# EE579_Skittles_sch.net
KiCad netlist of a schematic drawn in Altium Designer
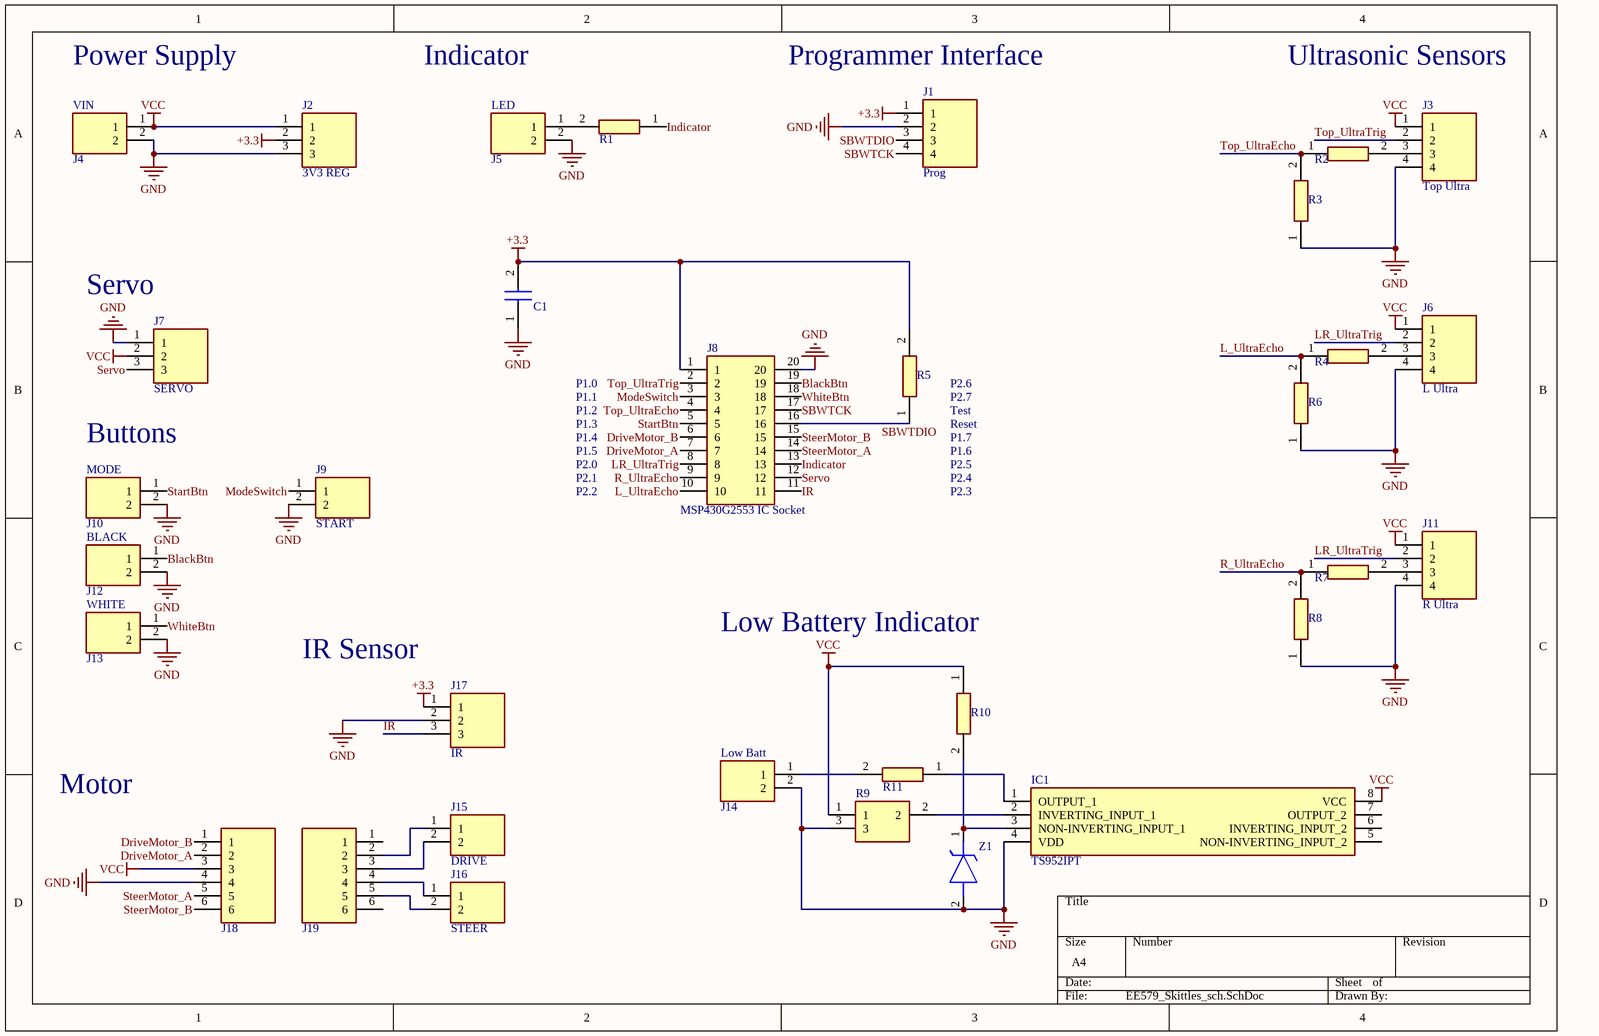
[diagram p0: EE579_Skittles_sch.SchDoc]

(export (version "E")
  (design (tool "Eeschema 10.0.6"))
  (components
    (comp (ref "C1")
      (value "21A106KQFNNNG")
      (footprint "PCB_lib:CAPC2012X135N")
      (description "Capacitor")
      (fields
        (field (name "MANUFACTURER_PART_NUMBER") "CL21A106KQFNNNG")
        (field (name "MOUSER PART NUMBER") "187-CL21A106KQFNNNG")
      )
      (libsource (lib "*") (part "CL21A106KQFNNNG"))
    )
    (comp (ref "IC1")
      (value "TS952IPT")
      (footprint "PCB_lib:SOP65P640X120-8N")
      (description "Integrated Circuit")
      (fields (field (name "MOUSER PART NUMBER") "511-TS952IP"))
      (libsource (lib "*") (part "TS952IPT"))
    )
    (comp (ref "J1")
      (value "Prog")
      (footprint "PCB_lib:HDRV4W64P0X254_1X4_1016X250X901P")
      (description "Connector")
      (fields
        (field (name "MANUFACTURER_PART_NUMBER") "PH1-04-UA")
        (field (name "MOUSER PART NUMBER") "737-PH1-04-UA")
      )
      (libsource (lib "*") (part "PH1-04-UA"))
    )
    (comp (ref "J2")
      (value "3V3 REG")
      (footprint "PCB_lib:RHDR3W60P0X254_1X3_762X254X700P")
      (description "Connector")
      (fields
        (field (name "MANUFACTURER_PART_NUMBER") "801-87-003-10-001101")
        (field (name "MOUSER PART NUMBER") "437-8018700310001101")
      )
      (libsource (lib "*") (part "801-87-003-10-001101"))
    )
    (comp (ref "J3")
      (value "Top Ultra")
      (footprint "PCB_lib:SHDR4W50P0X200_1X4_990X450X600P")
      (description "Connector")
      (fields (field (name "MANUFACTURER_PART_NUMBER") "B4B-PH-K-S(LF)(SN)"))
      (libsource (lib "*") (part "B4B-PH-K-S_LF__SN_"))
    )
    (comp (ref "J4")
      (value "VIN")
      (footprint "PCB_lib:SHDR2W50P0X200_1X2_590X450X600P")
      (description "Connector")
      (fields (field (name "MANUFACTURER_PART_NUMBER") "B2B-PH-K-S(LF)(SN)"))
      (libsource (lib "") (part "B2B-PH-K-S_LF__SN__1"))
    )
    (comp (ref "J5")
      (value "LED")
      (footprint "PCB_lib:SHDR2W50P0X200_1X2_590X450X600P")
      (description "Connector")
      (fields (field (name "MANUFACTURER_PART_NUMBER") "B2B-PH-K-S(LF)(SN)"))
      (libsource (lib "") (part "B2B-PH-K-S_LF__SN__1"))
    )
    (comp (ref "J6")
      (value "L Ultra")
      (footprint "PCB_lib:SHDR4W50P0X200_1X4_990X450X600P")
      (description "Connector")
      (fields (field (name "MANUFACTURER_PART_NUMBER") "B4B-PH-K-S(LF)(SN)"))
      (libsource (lib "*") (part "B4B-PH-K-S_LF__SN_"))
    )
    (comp (ref "J7")
      (value "SERVO")
      (footprint "PCB_lib:RHDR3W60P0X254_1X3_762X254X700P")
      (description "Connector")
      (fields
        (field (name "MANUFACTURER_PART_NUMBER") "801-87-003-10-001101")
        (field (name "MOUSER PART NUMBER") "437-8018700310001101")
      )
      (libsource (lib "*") (part "801-87-003-10-001101"))
    )
    (comp (ref "J8")
      (value "MSP430G2553 IC Socket")
      (footprint "PCB_lib:DIPS762W70P254L2540H510Q20N")
      (description "Connector")
      (fields
        (field (name "MANUFACTURER_PART_NUMBER") "1-2199298-6")
        (field (name "MOUSER PART NUMBER") "571-1-2199298-6")
      )
      (libsource (lib "*") (part "1-2199298-6"))
    )
    (comp (ref "J9")
      (value "START")
      (footprint "PCB_lib:SHDR2W50P0X200_1X2_590X450X600P")
      (description "Connector")
      (fields (field (name "MANUFACTURER_PART_NUMBER") "B2B-PH-K-S(LF)(SN)"))
      (libsource (lib "*") (part "B2B-PH-K-S_LF__SN_"))
    )
    (comp (ref "J10")
      (value "MODE")
      (footprint "PCB_lib:SHDR2W50P0X200_1X2_590X450X600P")
      (description "Connector")
      (fields (field (name "MANUFACTURER_PART_NUMBER") "B2B-PH-K-S(LF)(SN)"))
      (libsource (lib "") (part "B2B-PH-K-S_LF__SN__1"))
    )
    (comp (ref "J11")
      (value "R Ultra")
      (footprint "PCB_lib:SHDR4W50P0X200_1X4_990X450X600P")
      (description "Connector")
      (fields (field (name "MANUFACTURER_PART_NUMBER") "B4B-PH-K-S(LF)(SN)"))
      (libsource (lib "*") (part "B4B-PH-K-S_LF__SN_"))
    )
    (comp (ref "J12")
      (value "BLACK")
      (footprint "PCB_lib:SHDR2W50P0X200_1X2_590X450X600P")
      (description "Connector")
      (fields (field (name "MANUFACTURER_PART_NUMBER") "B2B-PH-K-S(LF)(SN)"))
      (libsource (lib "") (part "B2B-PH-K-S_LF__SN__1"))
    )
    (comp (ref "J13")
      (value "WHITE")
      (footprint "PCB_lib:SHDR2W50P0X200_1X2_590X450X600P")
      (description "Connector")
      (fields (field (name "MANUFACTURER_PART_NUMBER") "B2B-PH-K-S(LF)(SN)"))
      (libsource (lib "") (part "B2B-PH-K-S_LF__SN__1"))
    )
    (comp (ref "J14")
      (value "Low Batt")
      (footprint "PCB_lib:SHDR2W50P0X200_1X2_590X450X600P")
      (description "Connector")
      (fields (field (name "MANUFACTURER_PART_NUMBER") "B2B-PH-K-S(LF)(SN)"))
      (libsource (lib "") (part "B2B-PH-K-S_LF__SN__1"))
    )
    (comp (ref "J15")
      (value "DRIVE")
      (footprint "PCB_lib:SHDR2W50P0X200_1X2_590X450X600P")
      (description "Connector")
      (fields (field (name "MANUFACTURER_PART_NUMBER") "B2B-PH-K-S(LF)(SN)"))
      (libsource (lib "*") (part "B2B-PH-K-S_LF__SN_"))
    )
    (comp (ref "J16")
      (value "STEER")
      (footprint "PCB_lib:SHDR2W50P0X200_1X2_590X450X600P")
      (description "Connector")
      (fields (field (name "MANUFACTURER_PART_NUMBER") "B2B-PH-K-S(LF)(SN)"))
      (libsource (lib "*") (part "B2B-PH-K-S_LF__SN_"))
    )
    (comp (ref "J17")
      (value "IR")
      (footprint "PCB_lib:SHDR3W50P0X200_1X3_790X450X600P")
      (description "Connector")
      (fields (field (name "MANUFACTURER_PART_NUMBER") "B3B-PH-K-S(LF)(SN)"))
      (libsource (lib "*") (part "B3B-PH-K-S_LF__SN_"))
    )
    (comp (ref "J18")
      (value "61300611821")
      (footprint "RHDR6W97P0X254_1X6_1574X250X865P")
      (description "Connector")
      (fields (field (name "MOUSER PART NUMBER") "710-61300611821"))
      (libsource (lib "SCH_lib") (part "61300611821"))
    )
    (comp (ref "J19")
      (value "61300611821")
      (footprint "RHDR6W97P0X254_1X6_1574X250X865P")
      (description "Connector")
      (fields (field (name "MOUSER PART NUMBER") "710-61300611821"))
      (libsource (lib "") (part "61300611821_1"))
    )
    (comp (ref "R1")
      (value "ERJ-PB6B3002V")
      (footprint "PCB_lib:RESC2012X70N")
      (description "Resistor")
      (fields (field (name "MOUSER PART NUMBER") "667-ERJ-PB6B3002V"))
      (libsource (lib "") (part "ERJ-PB6B3002V_3"))
    )
    (comp (ref "R2")
      (value "ERJ-PB6B3002V")
      (footprint "PCB_lib:RESC2012X70N")
      (description "Resistor")
      (fields (field (name "MOUSER PART NUMBER") "667-ERJ-PB6B3002V"))
      (libsource (lib "") (part "ERJ-PB6B3002V_1"))
    )
    (comp (ref "R3")
      (value "ERJ-PB6B3002V")
      (footprint "PCB_lib:RESC2012X70N")
      (description "Resistor")
      (fields (field (name "MOUSER PART NUMBER") "667-ERJ-PB6B3002V"))
      (libsource (lib "*") (part "ERJ-PB6B3002V"))
    )
    (comp (ref "R4")
      (value "ERJ-PB6B3002V")
      (footprint "PCB_lib:RESC2012X70N")
      (description "Resistor")
      (fields (field (name "MOUSER PART NUMBER") "667-ERJ-PB6B3002V"))
      (libsource (lib "") (part "ERJ-PB6B3002V_1"))
    )
    (comp (ref "R5")
      (value "ERJ-PB6B3002V")
      (footprint "PCB_lib:RESC2012X70N")
      (description "Resistor")
      (fields (field (name "MOUSER PART NUMBER") "667-ERJ-PB6B3002V"))
      (libsource (lib "*") (part "ERJ-PB6B3002V"))
    )
    (comp (ref "R6")
      (value "ERJ-PB6B3002V")
      (footprint "PCB_lib:RESC2012X70N")
      (description "Resistor")
      (fields (field (name "MOUSER PART NUMBER") "667-ERJ-PB6B3002V"))
      (libsource (lib "*") (part "ERJ-PB6B3002V"))
    )
    (comp (ref "R7")
      (value "ERJ-PB6B3002V")
      (footprint "PCB_lib:RESC2012X70N")
      (description "Resistor")
      (fields (field (name "MOUSER PART NUMBER") "667-ERJ-PB6B3002V"))
      (libsource (lib "") (part "ERJ-PB6B3002V_1"))
    )
    (comp (ref "R8")
      (value "ERJ-PB6B3002V")
      (footprint "PCB_lib:RESC2012X70N")
      (description "Resistor")
      (fields (field (name "MOUSER PART NUMBER") "667-ERJ-PB6B3002V"))
      (libsource (lib "*") (part "ERJ-PB6B3002V"))
    )
    (comp (ref "R9")
      (value "3314G-1-103E")
      (footprint "PCB_lib:3314G-1-102E")
      (description "Resistor")
      (fields (field (name "MOUSER PART NUMBER") "652-3314G-1-103E"))
      (libsource (lib "*") (part "3314G-1-103E"))
    )
    (comp (ref "R10")
      (value "ERJ-PB6B3002V")
      (footprint "PCB_lib:RESC2012X70N")
      (description "Resistor")
      (fields (field (name "MOUSER PART NUMBER") "667-ERJ-PB6B3002V"))
      (libsource (lib "") (part "ERJ-PB6B3002V_2"))
    )
    (comp (ref "R11")
      (value "ERJ-PB6B3002V")
      (footprint "PCB_lib:RESC2012X70N")
      (description "Resistor")
      (fields (field (name "MOUSER PART NUMBER") "667-ERJ-PB6B3002V"))
      (libsource (lib "") (part "ERJ-PB6B3002V_3"))
    )
    (comp (ref "Z1")
      (value "BZT52C4V7-E3-08")
      (footprint "PCB_lib:SOD3716X135N")
      (description "Zener Diode")
      (fields (field (name "MOUSER PART NUMBER") "78-BZT52C4V7-E3-08"))
      (libsource (lib "*") (part "BZT52C4V7-E3-08"))
    )
  )
  (nets
    (net (code "1") (name "+3.3") (class "Default")
      (node (ref "C1") (pin "2") (pinfunction "2_2") (pintype "passive"))
      (node (ref "J1") (pin "1") (pinfunction "1_1") (pintype "passive"))
      (node (ref "J17") (pin "1") (pinfunction "1_1") (pintype "passive"))
      (node (ref "J2") (pin "2") (pinfunction "2_2") (pintype "passive"))
      (node (ref "J8") (pin "1") (pinfunction "1_1") (pintype "passive"))
      (node (ref "R5") (pin "2") (pinfunction "2_2") (pintype "passive"))
    )
    (net (code "2") (name "/BlackBtn") (class "Default")
      (node (ref "J12") (pin "1") (pinfunction "1_1") (pintype "passive"))
      (node (ref "J8") (pin "19") (pinfunction "19_19") (pintype "passive"))
    )
    (net (code "3") (name "/DriveMotor_A") (class "Default")
      (node (ref "J18") (pin "2") (pinfunction "2_2") (pintype "passive"))
      (node (ref "J8") (pin "7") (pinfunction "7_7") (pintype "passive"))
    )
    (net (code "4") (name "/DriveMotor_B") (class "Default")
      (node (ref "J18") (pin "1") (pinfunction "1_1") (pintype "passive"))
      (node (ref "J8") (pin "6") (pinfunction "6_6") (pintype "passive"))
    )
    (net (code "5") (name "/IR") (class "Default")
      (node (ref "J17") (pin "3") (pinfunction "3_3") (pintype "passive"))
      (node (ref "J8") (pin "11") (pinfunction "11_11") (pintype "passive"))
    )
    (net (code "6") (name "/Indicator") (class "Default")
      (node (ref "J8") (pin "13") (pinfunction "13_13") (pintype "passive"))
      (node (ref "R1") (pin "1") (pinfunction "1_1") (pintype "passive"))
    )
    (net (code "7") (name "/LR_UltraTrig") (class "Default")
      (node (ref "J11") (pin "2") (pinfunction "2_2") (pintype "passive"))
      (node (ref "J6") (pin "2") (pinfunction "2_2") (pintype "passive"))
      (node (ref "J8") (pin "8") (pinfunction "8_8") (pintype "passive"))
    )
    (net (code "8") (name "/L_UltraEcho") (class "Default")
      (node (ref "J8") (pin "10") (pinfunction "10_10") (pintype "passive"))
      (node (ref "R4") (pin "1") (pinfunction "1_1") (pintype "passive"))
      (node (ref "R6") (pin "2") (pinfunction "2_2") (pintype "passive"))
    )
    (net (code "9") (name "/ModeSwitch") (class "Default")
      (node (ref "J8") (pin "3") (pinfunction "3_3") (pintype "passive"))
      (node (ref "J9") (pin "1") (pinfunction "1_1") (pintype "passive"))
    )
    (net (code "10") (name "/R_UltraEcho") (class "Default")
      (node (ref "J8") (pin "9") (pinfunction "9_9") (pintype "passive"))
      (node (ref "R7") (pin "1") (pinfunction "1_1") (pintype "passive"))
      (node (ref "R8") (pin "2") (pinfunction "2_2") (pintype "passive"))
    )
    (net (code "11") (name "/SBWTCK") (class "Default")
      (node (ref "J1") (pin "4") (pinfunction "4_4") (pintype "passive"))
      (node (ref "J8") (pin "17") (pinfunction "17_17") (pintype "passive"))
    )
    (net (code "12") (name "/SBWTDIO") (class "Default")
      (node (ref "J1") (pin "3") (pinfunction "3_3") (pintype "passive"))
      (node (ref "J8") (pin "16") (pinfunction "16_16") (pintype "passive"))
      (node (ref "R5") (pin "1") (pinfunction "1_1") (pintype "passive"))
    )
    (net (code "13") (name "/Servo") (class "Default")
      (node (ref "J7") (pin "3") (pinfunction "3_3") (pintype "passive"))
      (node (ref "J8") (pin "12") (pinfunction "12_12") (pintype "passive"))
    )
    (net (code "14") (name "/StartBtn") (class "Default")
      (node (ref "J10") (pin "1") (pinfunction "1_1") (pintype "passive"))
      (node (ref "J8") (pin "5") (pinfunction "5_5") (pintype "passive"))
    )
    (net (code "15") (name "/SteerMotor_A") (class "Default")
      (node (ref "J18") (pin "5") (pinfunction "5_5") (pintype "passive"))
      (node (ref "J8") (pin "14") (pinfunction "14_14") (pintype "passive"))
    )
    (net (code "16") (name "/SteerMotor_B") (class "Default")
      (node (ref "J18") (pin "6") (pinfunction "6_6") (pintype "passive"))
      (node (ref "J8") (pin "15") (pinfunction "15_15") (pintype "passive"))
    )
    (net (code "17") (name "/Top_UltraEcho") (class "Default")
      (node (ref "J8") (pin "4") (pinfunction "4_4") (pintype "passive"))
      (node (ref "R2") (pin "1") (pinfunction "1_1") (pintype "passive"))
      (node (ref "R3") (pin "2") (pinfunction "2_2") (pintype "passive"))
    )
    (net (code "18") (name "/Top_UltraTrig") (class "Default")
      (node (ref "J3") (pin "2") (pinfunction "2_2") (pintype "passive"))
      (node (ref "J8") (pin "2") (pinfunction "2_2") (pintype "passive"))
    )
    (net (code "19") (name "/WhiteBtn") (class "Default")
      (node (ref "J13") (pin "1") (pinfunction "1_1") (pintype "passive"))
      (node (ref "J8") (pin "18") (pinfunction "18_18") (pintype "passive"))
    )
    (net (code "20") (name "GND") (class "Default")
      (node (ref "C1") (pin "1") (pinfunction "1_1") (pintype "passive"))
      (node (ref "IC1") (pin "4") (pinfunction "VDD_4") (pintype "passive"))
      (node (ref "J1") (pin "2") (pinfunction "2_2") (pintype "passive"))
      (node (ref "J10") (pin "2") (pinfunction "2_2") (pintype "passive"))
      (node (ref "J11") (pin "4") (pinfunction "4_4") (pintype "passive"))
      (node (ref "J12") (pin "2") (pinfunction "2_2") (pintype "passive"))
      (node (ref "J13") (pin "2") (pinfunction "2_2") (pintype "passive"))
      (node (ref "J14") (pin "2") (pinfunction "2_2") (pintype "passive"))
      (node (ref "J17") (pin "2") (pinfunction "2_2") (pintype "passive"))
      (node (ref "J18") (pin "4") (pinfunction "4_4") (pintype "passive"))
      (node (ref "J2") (pin "3") (pinfunction "3_3") (pintype "passive"))
      (node (ref "J3") (pin "4") (pinfunction "4_4") (pintype "passive"))
      (node (ref "J4") (pin "2") (pinfunction "2_2") (pintype "passive"))
      (node (ref "J5") (pin "2") (pinfunction "2_2") (pintype "passive"))
      (node (ref "J6") (pin "4") (pinfunction "4_4") (pintype "passive"))
      (node (ref "J7") (pin "1") (pinfunction "1_1") (pintype "passive"))
      (node (ref "J8") (pin "20") (pinfunction "20_20") (pintype "passive"))
      (node (ref "J9") (pin "2") (pinfunction "2_2") (pintype "passive"))
      (node (ref "R3") (pin "1") (pinfunction "1_1") (pintype "passive"))
      (node (ref "R6") (pin "1") (pinfunction "1_1") (pintype "passive"))
      (node (ref "R8") (pin "1") (pinfunction "1_1") (pintype "passive"))
      (node (ref "R9") (pin "3") (pinfunction "3_3") (pintype "passive"))
      (node (ref "Z1") (pin "2") (pinfunction "A_2") (pintype "passive"))
    )
    (net (code "21") (name "Net-(IC1-INVERTING_INPUT_1)") (class "Default")
      (node (ref "IC1") (pin "2") (pinfunction "INVERTING_INPUT_1_2") (pintype "passive"))
      (node (ref "R9") (pin "2") (pinfunction "2_2") (pintype "passive"))
    )
    (net (code "22") (name "Net-(IC1-NON-INVERTING_INPUT_1)") (class "Default")
      (node (ref "IC1") (pin "3") (pinfunction "NON-INVERTING_INPUT_1_3") (pintype "passive"))
      (node (ref "R10") (pin "2") (pinfunction "2_2") (pintype "passive"))
      (node (ref "Z1") (pin "1") (pinfunction "K_1") (pintype "passive"))
    )
    (net (code "23") (name "Net-(IC1-OUTPUT_1)") (class "Default")
      (node (ref "IC1") (pin "1") (pinfunction "OUTPUT_1_1") (pintype "passive"))
      (node (ref "R11") (pin "1") (pinfunction "1_1") (pintype "passive"))
    )
    (net (code "24") (name "Net-(J3-Pad3)") (class "Default")
      (node (ref "J3") (pin "3") (pinfunction "3_3") (pintype "passive"))
      (node (ref "R2") (pin "2") (pinfunction "2_2") (pintype "passive"))
    )
    (net (code "25") (name "Net-(J5-Pad1)") (class "Default")
      (node (ref "J5") (pin "1") (pinfunction "1_1") (pintype "passive"))
      (node (ref "R1") (pin "2") (pinfunction "2_2") (pintype "passive"))
    )
    (net (code "26") (name "Net-(J6-Pad3)") (class "Default")
      (node (ref "J6") (pin "3") (pinfunction "3_3") (pintype "passive"))
      (node (ref "R4") (pin "2") (pinfunction "2_2") (pintype "passive"))
    )
    (net (code "27") (name "Net-(J11-Pad3)") (class "Default")
      (node (ref "J11") (pin "3") (pinfunction "3_3") (pintype "passive"))
      (node (ref "R7") (pin "2") (pinfunction "2_2") (pintype "passive"))
    )
    (net (code "28") (name "Net-(J14-Pad1)") (class "Default")
      (node (ref "J14") (pin "1") (pinfunction "1_1") (pintype "passive"))
      (node (ref "R11") (pin "2") (pinfunction "2_2") (pintype "passive"))
    )
    (net (code "29") (name "Net-(J15-Pad1)") (class "Default")
      (node (ref "J15") (pin "1") (pinfunction "1_1") (pintype "passive"))
      (node (ref "J19") (pin "2") (pinfunction "2_2") (pintype "passive"))
    )
    (net (code "30") (name "Net-(J15-Pad2)") (class "Default")
      (node (ref "J15") (pin "2") (pinfunction "2_2") (pintype "passive"))
      (node (ref "J19") (pin "3") (pinfunction "3_3") (pintype "passive"))
    )
    (net (code "31") (name "Net-(J16-Pad1)") (class "Default")
      (node (ref "J16") (pin "1") (pinfunction "1_1") (pintype "passive"))
      (node (ref "J19") (pin "4") (pinfunction "4_4") (pintype "passive"))
    )
    (net (code "32") (name "Net-(J16-Pad2)") (class "Default")
      (node (ref "J16") (pin "2") (pinfunction "2_2") (pintype "passive"))
      (node (ref "J19") (pin "5") (pinfunction "5_5") (pintype "passive"))
    )
    (net (code "33") (name "VCC") (class "Default")
      (node (ref "IC1") (pin "8") (pinfunction "VCC_8") (pintype "passive"))
      (node (ref "J11") (pin "1") (pinfunction "1_1") (pintype "passive"))
      (node (ref "J18") (pin "3") (pinfunction "3_3") (pintype "passive"))
      (node (ref "J2") (pin "1") (pinfunction "1_1") (pintype "passive"))
      (node (ref "J3") (pin "1") (pinfunction "1_1") (pintype "passive"))
      (node (ref "J4") (pin "1") (pinfunction "1_1") (pintype "passive"))
      (node (ref "J6") (pin "1") (pinfunction "1_1") (pintype "passive"))
      (node (ref "J7") (pin "2") (pinfunction "2_2") (pintype "passive"))
      (node (ref "R10") (pin "1") (pinfunction "1_1") (pintype "passive"))
      (node (ref "R9") (pin "1") (pinfunction "1_1") (pintype "passive"))
    )
    (net (code "34") (name "unconnected-(IC1-INVERTING_INPUT_2-Pad6)") (class "Default")
      (node (ref "IC1") (pin "6") (pinfunction "INVERTING_INPUT_2_6") (pintype "passive"))
    )
    (net (code "35") (name "unconnected-(IC1-NON-INVERTING_INPUT_2-Pad5)") (class "Default")
      (node (ref "IC1") (pin "5") (pinfunction "NON-INVERTING_INPUT_2_5") (pintype "passive"))
    )
    (net (code "36") (name "unconnected-(IC1-OUTPUT_2-Pad7)") (class "Default")
      (node (ref "IC1") (pin "7") (pinfunction "OUTPUT_2_7") (pintype "passive"))
    )
    (net (code "37") (name "unconnected-(J19-Pad1)") (class "Default")
      (node (ref "J19") (pin "1") (pinfunction "1_1") (pintype "passive"))
    )
    (net (code "38") (name "unconnected-(J19-Pad6)") (class "Default")
      (node (ref "J19") (pin "6") (pinfunction "6_6") (pintype "passive"))
    )
  )
)
